# projeto_eagle.net
KiCad netlist of a schematic drawn in EAGLE
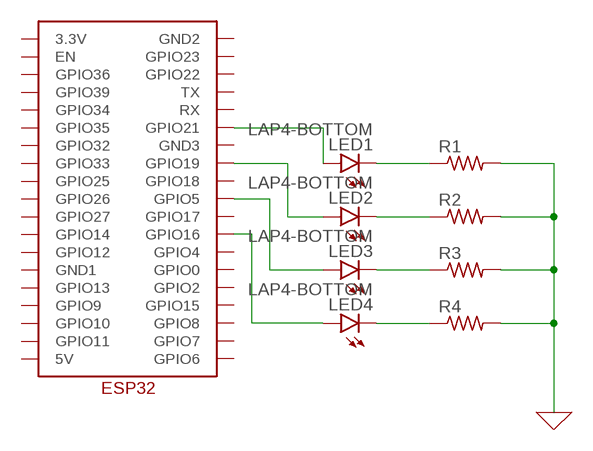
[diagram p0: schematic, sheet 1]

(export (version "E")
  (design (tool "Eeschema 10.0.6"))
  (components
    (comp (ref "LED1")
      (value "LAP4-BOTTOM")
      (footprint "eagle-import:P47F-BOTTOM")
      (libsource (lib "eagle-import") (part "P4-BOTTOMLA"))
    )
    (comp (ref "LED2")
      (value "LAP4-BOTTOM")
      (footprint "eagle-import:P47F-BOTTOM")
      (libsource (lib "eagle-import") (part "P4-BOTTOMLA"))
    )
    (comp (ref "LED3")
      (value "LAP4-BOTTOM")
      (footprint "eagle-import:P47F-BOTTOM")
      (libsource (lib "eagle-import") (part "P4-BOTTOMLA"))
    )
    (comp (ref "LED4")
      (value "LAP4-BOTTOM")
      (footprint "eagle-import:P47F-BOTTOM")
      (libsource (lib "eagle-import") (part "P4-BOTTOMLA"))
    )
    (comp (ref "R1")
      (value "R-US_0204/2V")
      (footprint "eagle-import:0204V")
      (libsource (lib "eagle-import") (part "R-US_0204/2V"))
    )
    (comp (ref "R2")
      (value "R-US_0204/2V")
      (footprint "eagle-import:0204V")
      (libsource (lib "eagle-import") (part "R-US_0204/2V"))
    )
    (comp (ref "R3")
      (value "R-US_0204/2V")
      (footprint "eagle-import:0204V")
      (libsource (lib "eagle-import") (part "R-US_0204/2V"))
    )
    (comp (ref "R4")
      (value "R-US_0204/2V")
      (footprint "eagle-import:0204V")
      (libsource (lib "eagle-import") (part "R-US_0204/2V"))
    )
    (comp (ref "U$1")
      (value "ESP32")
      (footprint "eagle-import:ESP32")
      (libsource (lib "eagle-import") (part "ESP32"))
    )
  )
  (nets
    (net (code "1") (name "GND") (class "Default")
      (node (ref "R1") (pin "2") (pinfunction "2_2") (pintype "passive"))
      (node (ref "R2") (pin "2") (pinfunction "2_2") (pintype "passive"))
      (node (ref "R3") (pin "2") (pinfunction "2_2") (pintype "passive"))
      (node (ref "R4") (pin "2") (pinfunction "2_2") (pintype "passive"))
    )
    (net (code "2") (name "Net-(LED1-PadA)") (class "Default")
      (node (ref "LED1") (pin "A") (pinfunction "A_A") (pintype "passive"))
      (node (ref "U$1") (pin "GPIO21") (pinfunction "GPIO21_GPIO21") (pintype "bidirectional"))
    )
    (net (code "3") (name "Net-(LED1-PadC)") (class "Default")
      (node (ref "LED1") (pin "C") (pinfunction "C_C") (pintype "passive"))
      (node (ref "R1") (pin "1") (pinfunction "1_1") (pintype "passive"))
    )
    (net (code "4") (name "Net-(LED2-PadA)") (class "Default")
      (node (ref "LED2") (pin "A") (pinfunction "A_A") (pintype "passive"))
      (node (ref "U$1") (pin "GPIO19") (pinfunction "GPIO19_GPIO19") (pintype "bidirectional"))
    )
    (net (code "5") (name "Net-(LED2-PadC)") (class "Default")
      (node (ref "LED2") (pin "C") (pinfunction "C_C") (pintype "passive"))
      (node (ref "R2") (pin "1") (pinfunction "1_1") (pintype "passive"))
    )
    (net (code "6") (name "Net-(LED3-PadA)") (class "Default")
      (node (ref "LED3") (pin "A") (pinfunction "A_A") (pintype "passive"))
      (node (ref "U$1") (pin "GPIO5") (pinfunction "GPIO5_GPIO5") (pintype "bidirectional"))
    )
    (net (code "7") (name "Net-(LED3-PadC)") (class "Default")
      (node (ref "LED3") (pin "C") (pinfunction "C_C") (pintype "passive"))
      (node (ref "R3") (pin "1") (pinfunction "1_1") (pintype "passive"))
    )
    (net (code "8") (name "Net-(LED4-PadA)") (class "Default")
      (node (ref "LED4") (pin "A") (pinfunction "A_A") (pintype "passive"))
      (node (ref "U$1") (pin "GPIO16") (pinfunction "GPIO16_GPIO16") (pintype "bidirectional"))
    )
    (net (code "9") (name "Net-(LED4-PadC)") (class "Default")
      (node (ref "LED4") (pin "C") (pinfunction "C_C") (pintype "passive"))
      (node (ref "R4") (pin "1") (pinfunction "1_1") (pintype "passive"))
    )
    (net (code "10") (name "unconnected-(U$1-Pad3.3V)") (class "Default")
      (node (ref "U$1") (pin "3.3V") (pinfunction "3.3V_3.3V") (pintype "bidirectional"))
    )
    (net (code "11") (name "unconnected-(U$1-Pad5V)") (class "Default")
      (node (ref "U$1") (pin "5V") (pinfunction "5V_5V") (pintype "bidirectional"))
    )
    (net (code "12") (name "unconnected-(U$1-PadEN)") (class "Default")
      (node (ref "U$1") (pin "EN") (pinfunction "EN_EN") (pintype "bidirectional"))
    )
    (net (code "13") (name "unconnected-(U$1-PadGND1)") (class "Default")
      (node (ref "U$1") (pin "GND1") (pinfunction "GND1_GND1") (pintype "bidirectional"))
    )
    (net (code "14") (name "unconnected-(U$1-PadGND2)") (class "Default")
      (node (ref "U$1") (pin "GND2") (pinfunction "GND2_GND2") (pintype "bidirectional"))
    )
    (net (code "15") (name "unconnected-(U$1-PadGND3)") (class "Default")
      (node (ref "U$1") (pin "GND3") (pinfunction "GND3_GND3") (pintype "bidirectional"))
    )
    (net (code "16") (name "unconnected-(U$1-PadGPIO0)") (class "Default")
      (node (ref "U$1") (pin "GPIO0") (pinfunction "GPIO0_GPIO0") (pintype "bidirectional"))
    )
    (net (code "17") (name "unconnected-(U$1-PadGPIO2)") (class "Default")
      (node (ref "U$1") (pin "GPIO2") (pinfunction "GPIO2_GPIO2") (pintype "bidirectional"))
    )
    (net (code "18") (name "unconnected-(U$1-PadGPIO4)") (class "Default")
      (node (ref "U$1") (pin "GPIO4") (pinfunction "GPIO4_GPIO4") (pintype "bidirectional"))
    )
    (net (code "19") (name "unconnected-(U$1-PadGPIO6)") (class "Default")
      (node (ref "U$1") (pin "GPIO6") (pinfunction "GPIO6_GPIO6") (pintype "bidirectional"))
    )
    (net (code "20") (name "unconnected-(U$1-PadGPIO7)") (class "Default")
      (node (ref "U$1") (pin "GPIO7") (pinfunction "GPIO7_GPIO7") (pintype "bidirectional"))
    )
    (net (code "21") (name "unconnected-(U$1-PadGPIO8)") (class "Default")
      (node (ref "U$1") (pin "GPIO8") (pinfunction "GPIO8_GPIO8") (pintype "bidirectional"))
    )
    (net (code "22") (name "unconnected-(U$1-PadGPIO9)") (class "Default")
      (node (ref "U$1") (pin "GPIO9") (pinfunction "GPIO9_GPIO9") (pintype "bidirectional"))
    )
    (net (code "23") (name "unconnected-(U$1-PadGPIO10)") (class "Default")
      (node (ref "U$1") (pin "GPIO10") (pinfunction "GPIO10_GPIO10") (pintype "bidirectional"))
    )
    (net (code "24") (name "unconnected-(U$1-PadGPIO11)") (class "Default")
      (node (ref "U$1") (pin "GPIO11") (pinfunction "GPIO11_GPIO11") (pintype "bidirectional"))
    )
    (net (code "25") (name "unconnected-(U$1-PadGPIO12)") (class "Default")
      (node (ref "U$1") (pin "GPIO12") (pinfunction "GPIO12_GPIO12") (pintype "bidirectional"))
    )
    (net (code "26") (name "unconnected-(U$1-PadGPIO13)") (class "Default")
      (node (ref "U$1") (pin "GPIO13") (pinfunction "GPIO13_GPIO13") (pintype "bidirectional"))
    )
    (net (code "27") (name "unconnected-(U$1-PadGPIO14)") (class "Default")
      (node (ref "U$1") (pin "GPIO14") (pinfunction "GPIO14_GPIO14") (pintype "bidirectional"))
    )
    (net (code "28") (name "unconnected-(U$1-PadGPIO15)") (class "Default")
      (node (ref "U$1") (pin "GPIO15") (pinfunction "GPIO15_GPIO15") (pintype "bidirectional"))
    )
    (net (code "29") (name "unconnected-(U$1-PadGPIO17)") (class "Default")
      (node (ref "U$1") (pin "GPIO17") (pinfunction "GPIO17_GPIO17") (pintype "bidirectional"))
    )
    (net (code "30") (name "unconnected-(U$1-PadGPIO18)") (class "Default")
      (node (ref "U$1") (pin "GPIO18") (pinfunction "GPIO18_GPIO18") (pintype "bidirectional"))
    )
    (net (code "31") (name "unconnected-(U$1-PadGPIO22)") (class "Default")
      (node (ref "U$1") (pin "GPIO22") (pinfunction "GPIO22_GPIO22") (pintype "bidirectional"))
    )
    (net (code "32") (name "unconnected-(U$1-PadGPIO23)") (class "Default")
      (node (ref "U$1") (pin "GPIO23") (pinfunction "GPIO23_GPIO23") (pintype "bidirectional"))
    )
    (net (code "33") (name "unconnected-(U$1-PadGPIO25)") (class "Default")
      (node (ref "U$1") (pin "GPIO25") (pinfunction "GPIO25_GPIO25") (pintype "bidirectional"))
    )
    (net (code "34") (name "unconnected-(U$1-PadGPIO26)") (class "Default")
      (node (ref "U$1") (pin "GPIO26") (pinfunction "GPIO26_GPIO26") (pintype "bidirectional"))
    )
    (net (code "35") (name "unconnected-(U$1-PadGPIO27)") (class "Default")
      (node (ref "U$1") (pin "GPIO27") (pinfunction "GPIO27_GPIO27") (pintype "bidirectional"))
    )
    (net (code "36") (name "unconnected-(U$1-PadGPIO32)") (class "Default")
      (node (ref "U$1") (pin "GPIO32") (pinfunction "GPIO32_GPIO32") (pintype "bidirectional"))
    )
    (net (code "37") (name "unconnected-(U$1-PadGPIO33)") (class "Default")
      (node (ref "U$1") (pin "GPIO33") (pinfunction "GPIO33_GPIO33") (pintype "bidirectional"))
    )
    (net (code "38") (name "unconnected-(U$1-PadGPIO34)") (class "Default")
      (node (ref "U$1") (pin "GPIO34") (pinfunction "GPIO34_GPIO34") (pintype "bidirectional"))
    )
    (net (code "39") (name "unconnected-(U$1-PadGPIO35)") (class "Default")
      (node (ref "U$1") (pin "GPIO35") (pinfunction "GPIO35_GPIO35") (pintype "bidirectional"))
    )
    (net (code "40") (name "unconnected-(U$1-PadGPIO36)") (class "Default")
      (node (ref "U$1") (pin "GPIO36") (pinfunction "GPIO36_GPIO36") (pintype "bidirectional"))
    )
    (net (code "41") (name "unconnected-(U$1-PadGPIO39)") (class "Default")
      (node (ref "U$1") (pin "GPIO39") (pinfunction "GPIO39_GPIO39") (pintype "bidirectional"))
    )
    (net (code "42") (name "unconnected-(U$1-PadRX)") (class "Default")
      (node (ref "U$1") (pin "RX") (pinfunction "RX_RX") (pintype "bidirectional"))
    )
    (net (code "43") (name "unconnected-(U$1-PadTX)") (class "Default")
      (node (ref "U$1") (pin "TX") (pinfunction "TX_TX") (pintype "bidirectional"))
    )
  )
)
